# fatayshield.net
KiCad netlist of a schematic drawn in EAGLE
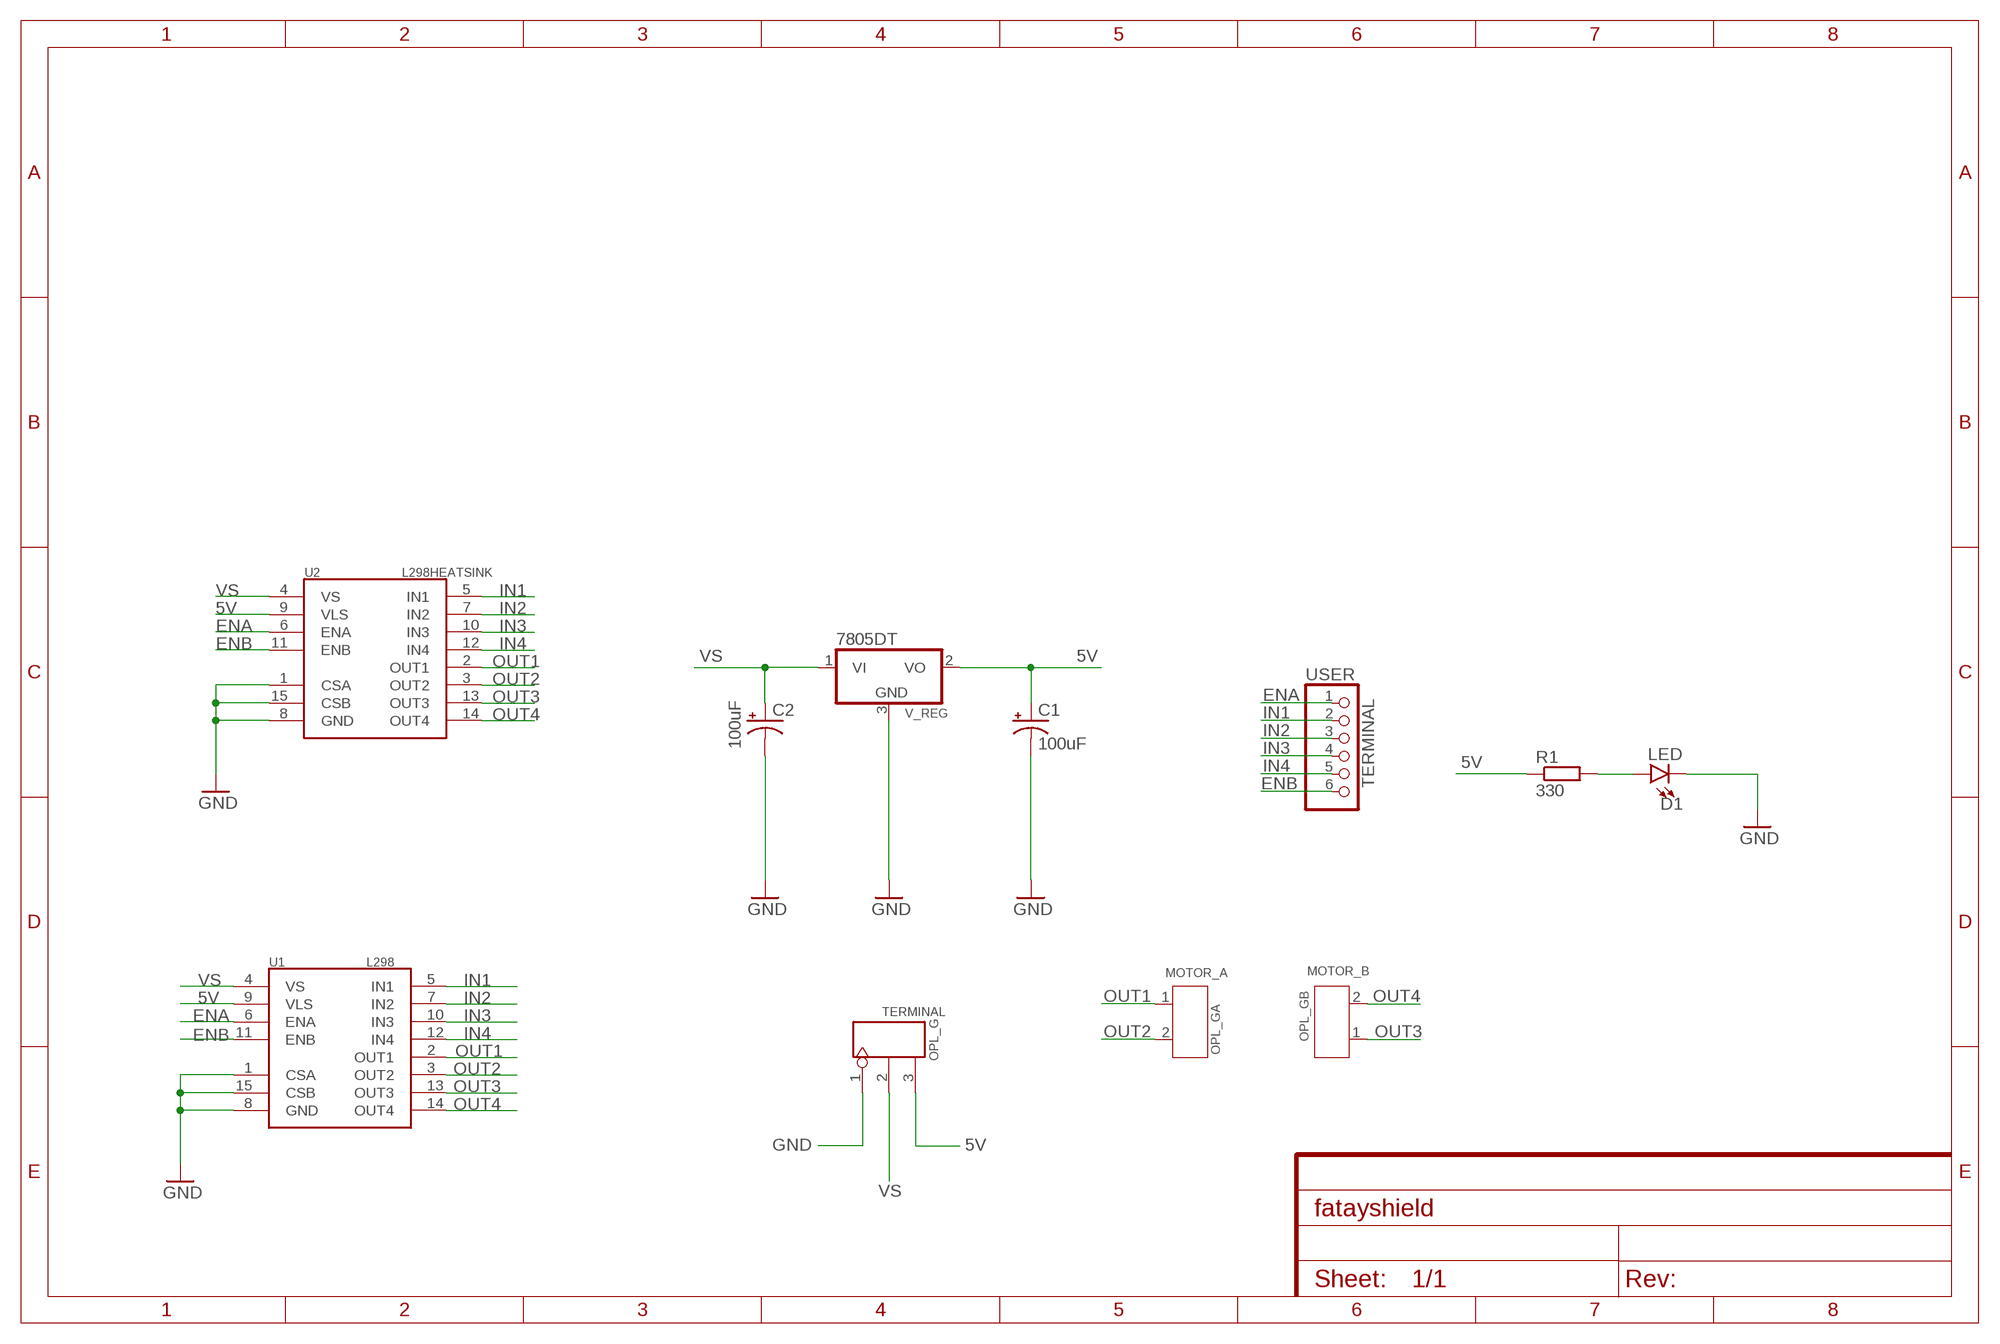
[diagram p0: schematic, sheet 1]

(export (version "E")
  (design (tool "Eeschema 10.0.6"))
  (components
    (comp (ref "C1")
      (value "100uF")
      (footprint "eagle-import:PANASONIC_D")
      (libsource (lib "eagle-import") (part "CPOL-USD"))
    )
    (comp (ref "C2")
      (value "100uF")
      (footprint "eagle-import:PANASONIC_D")
      (libsource (lib "eagle-import") (part "CPOL-USD"))
    )
    (comp (ref "D1")
      (value "LED")
      (footprint "eagle-import:LED-0603")
      (libsource (lib "eagle-import") (part "LED-RED0603"))
    )
    (comp (ref "OPL_GA")
      (value "MOTOR_A")
      (footprint "eagle-import:H2-3.5-7.0X7.0MM")
      (libsource (lib "eagle-import") (part "SCREW-TERMINAL-GREEN(2P-3.5)"))
    )
    (comp (ref "OPL_GB")
      (value "MOTOR_B")
      (footprint "eagle-import:H2-3.5-7.0X7.0MM")
      (libsource (lib "eagle-import") (part "SCREW-TERMINAL-GREEN(2P-3.5)"))
    )
    (comp (ref "R1")
      (value "330")
      (footprint "eagle-import:R0805")
      (libsource (lib "eagle-import") (part "R-EU_R0805"))
    )
    (comp (ref "TERMINAL")
      (value "OPL_G")
      (footprint "eagle-import:H3-5.0-15.5X8.0MM")
      (libsource (lib "eagle-import") (part "SCREW-TERMINAL-GREEN(3P-5.0)"))
    )
    (comp (ref "U1")
      (value "L298")
      (footprint "eagle-import:MULTIWATT15")
      (libsource (lib "eagle-import") (part "L298"))
    )
    (comp (ref "U2")
      (value "L298HEATSINK")
      (footprint "eagle-import:MULTIWATT15_6400BGHEATSINK")
      (libsource (lib "eagle-import") (part "L298HEATSINK"))
    )
    (comp (ref "USER")
      (value "TERMINAL")
      (footprint "eagle-import:1X06-3.5MM")
      (libsource (lib "eagle-import") (part "PINHD-1X6-3.5MM"))
    )
    (comp (ref "V_REG")
      (value "7805DT")
      (footprint "eagle-import:TO252")
      (libsource (lib "eagle-import") (part "78DT05"))
    )
  )
  (nets
    (net (code "1") (name "/5V") (class "Default")
      (node (ref "C1") (pin "+") (pinfunction "+_+") (pintype "passive"))
      (node (ref "R1") (pin "1") (pinfunction "1_1") (pintype "passive"))
      (node (ref "TERMINAL") (pin "3") (pinfunction "P$3_3") (pintype "bidirectional"))
      (node (ref "U1") (pin "9") (pinfunction "VLS_9") (pintype "bidirectional"))
      (node (ref "U2") (pin "9") (pinfunction "VLS_9") (pintype "bidirectional"))
      (node (ref "V_REG") (pin "2") (pinfunction "VO_2") (pintype "passive"))
    )
    (net (code "2") (name "/ENA") (class "Default")
      (node (ref "U1") (pin "6") (pinfunction "ENA_6") (pintype "bidirectional"))
      (node (ref "U2") (pin "6") (pinfunction "ENA_6") (pintype "bidirectional"))
      (node (ref "USER") (pin "1") (pinfunction "1_1") (pintype "passive"))
    )
    (net (code "3") (name "/ENB") (class "Default")
      (node (ref "U1") (pin "11") (pinfunction "ENB_11") (pintype "bidirectional"))
      (node (ref "U2") (pin "11") (pinfunction "ENB_11") (pintype "bidirectional"))
      (node (ref "USER") (pin "6") (pinfunction "6_6") (pintype "passive"))
    )
    (net (code "4") (name "/IN1") (class "Default")
      (node (ref "U1") (pin "5") (pinfunction "IN1_5") (pintype "bidirectional"))
      (node (ref "U2") (pin "5") (pinfunction "IN1_5") (pintype "bidirectional"))
      (node (ref "USER") (pin "2") (pinfunction "2_2") (pintype "passive"))
    )
    (net (code "5") (name "/IN2") (class "Default")
      (node (ref "U1") (pin "7") (pinfunction "IN2_7") (pintype "bidirectional"))
      (node (ref "U2") (pin "7") (pinfunction "IN2_7") (pintype "bidirectional"))
      (node (ref "USER") (pin "3") (pinfunction "3_3") (pintype "passive"))
    )
    (net (code "6") (name "/IN3") (class "Default")
      (node (ref "U1") (pin "10") (pinfunction "IN3_10") (pintype "bidirectional"))
      (node (ref "U2") (pin "10") (pinfunction "IN3_10") (pintype "bidirectional"))
      (node (ref "USER") (pin "4") (pinfunction "4_4") (pintype "passive"))
    )
    (net (code "7") (name "/IN4") (class "Default")
      (node (ref "U1") (pin "12") (pinfunction "IN4_12") (pintype "bidirectional"))
      (node (ref "U2") (pin "12") (pinfunction "IN4_12") (pintype "bidirectional"))
      (node (ref "USER") (pin "5") (pinfunction "5_5") (pintype "passive"))
    )
    (net (code "8") (name "/OUT1") (class "Default")
      (node (ref "OPL_GA") (pin "1") (pinfunction "1_1") (pintype "bidirectional"))
      (node (ref "U1") (pin "2") (pinfunction "OUT1_2") (pintype "bidirectional"))
      (node (ref "U2") (pin "2") (pinfunction "OUT1_2") (pintype "bidirectional"))
    )
    (net (code "9") (name "/OUT2") (class "Default")
      (node (ref "OPL_GA") (pin "2") (pinfunction "2_2") (pintype "bidirectional"))
      (node (ref "U1") (pin "3") (pinfunction "OUT2_3") (pintype "bidirectional"))
      (node (ref "U2") (pin "3") (pinfunction "OUT2_3") (pintype "bidirectional"))
    )
    (net (code "10") (name "/OUT3") (class "Default")
      (node (ref "OPL_GB") (pin "1") (pinfunction "1_1") (pintype "bidirectional"))
      (node (ref "U1") (pin "13") (pinfunction "OUT3_13") (pintype "bidirectional"))
      (node (ref "U2") (pin "13") (pinfunction "OUT3_13") (pintype "bidirectional"))
    )
    (net (code "11") (name "/OUT4") (class "Default")
      (node (ref "OPL_GB") (pin "2") (pinfunction "2_2") (pintype "bidirectional"))
      (node (ref "U1") (pin "14") (pinfunction "OUT4_14") (pintype "bidirectional"))
      (node (ref "U2") (pin "14") (pinfunction "OUT4_14") (pintype "bidirectional"))
    )
    (net (code "12") (name "/VS") (class "Default")
      (node (ref "C2") (pin "+") (pinfunction "+_+") (pintype "passive"))
      (node (ref "TERMINAL") (pin "2") (pinfunction "P$2_2") (pintype "bidirectional"))
      (node (ref "U1") (pin "4") (pinfunction "VS_4") (pintype "bidirectional"))
      (node (ref "U2") (pin "4") (pinfunction "VS_4") (pintype "bidirectional"))
      (node (ref "V_REG") (pin "1") (pinfunction "VI_1") (pintype "input"))
    )
    (net (code "13") (name "GND") (class "Default")
      (node (ref "C1") (pin "-") (pinfunction "-_-") (pintype "passive"))
      (node (ref "C2") (pin "-") (pinfunction "-_-") (pintype "passive"))
      (node (ref "D1") (pin "C") (pinfunction "C_C") (pintype "passive"))
      (node (ref "TERMINAL") (pin "1") (pinfunction "P$1_1") (pintype "bidirectional"))
      (node (ref "U1") (pin "1") (pinfunction "CSA_1") (pintype "bidirectional"))
      (node (ref "U1") (pin "15") (pinfunction "CSB_15") (pintype "bidirectional"))
      (node (ref "U1") (pin "8") (pinfunction "GND_8") (pintype "bidirectional"))
      (node (ref "U2") (pin "1") (pinfunction "CSA_1") (pintype "bidirectional"))
      (node (ref "U2") (pin "15") (pinfunction "CSB_15") (pintype "bidirectional"))
      (node (ref "U2") (pin "8") (pinfunction "GND_8") (pintype "bidirectional"))
      (node (ref "V_REG") (pin "3") (pinfunction "GND_3") (pintype "passive"))
    )
    (net (code "14") (name "Net-(D1-PadA)") (class "Default")
      (node (ref "D1") (pin "A") (pinfunction "A_A") (pintype "passive"))
      (node (ref "R1") (pin "2") (pinfunction "2_2") (pintype "passive"))
    )
  )
)
